# UI_PCB.net
KiCad netlist of a schematic drawn in EAGLE
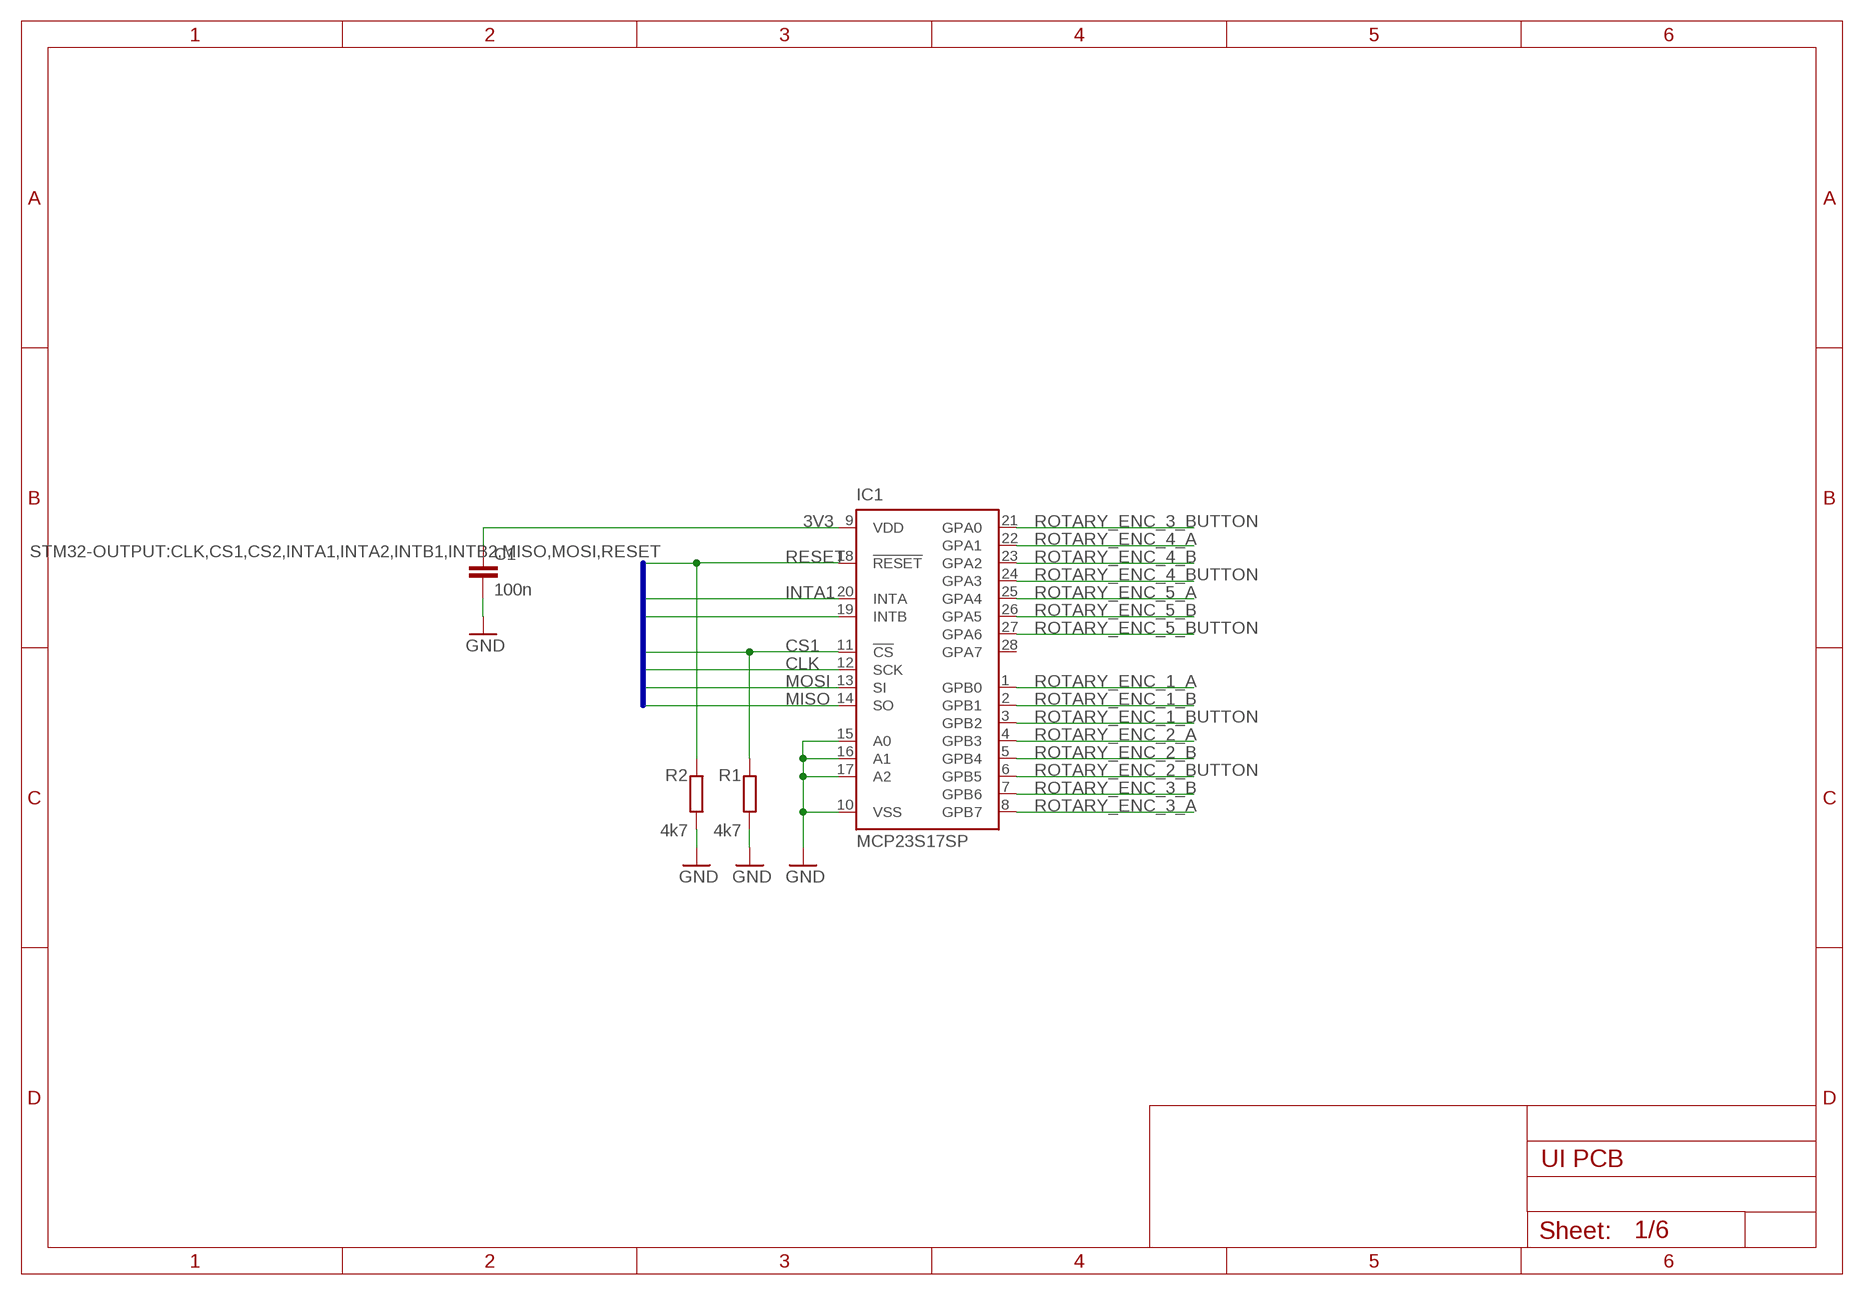
[diagram p0: schematic, sheet 1]
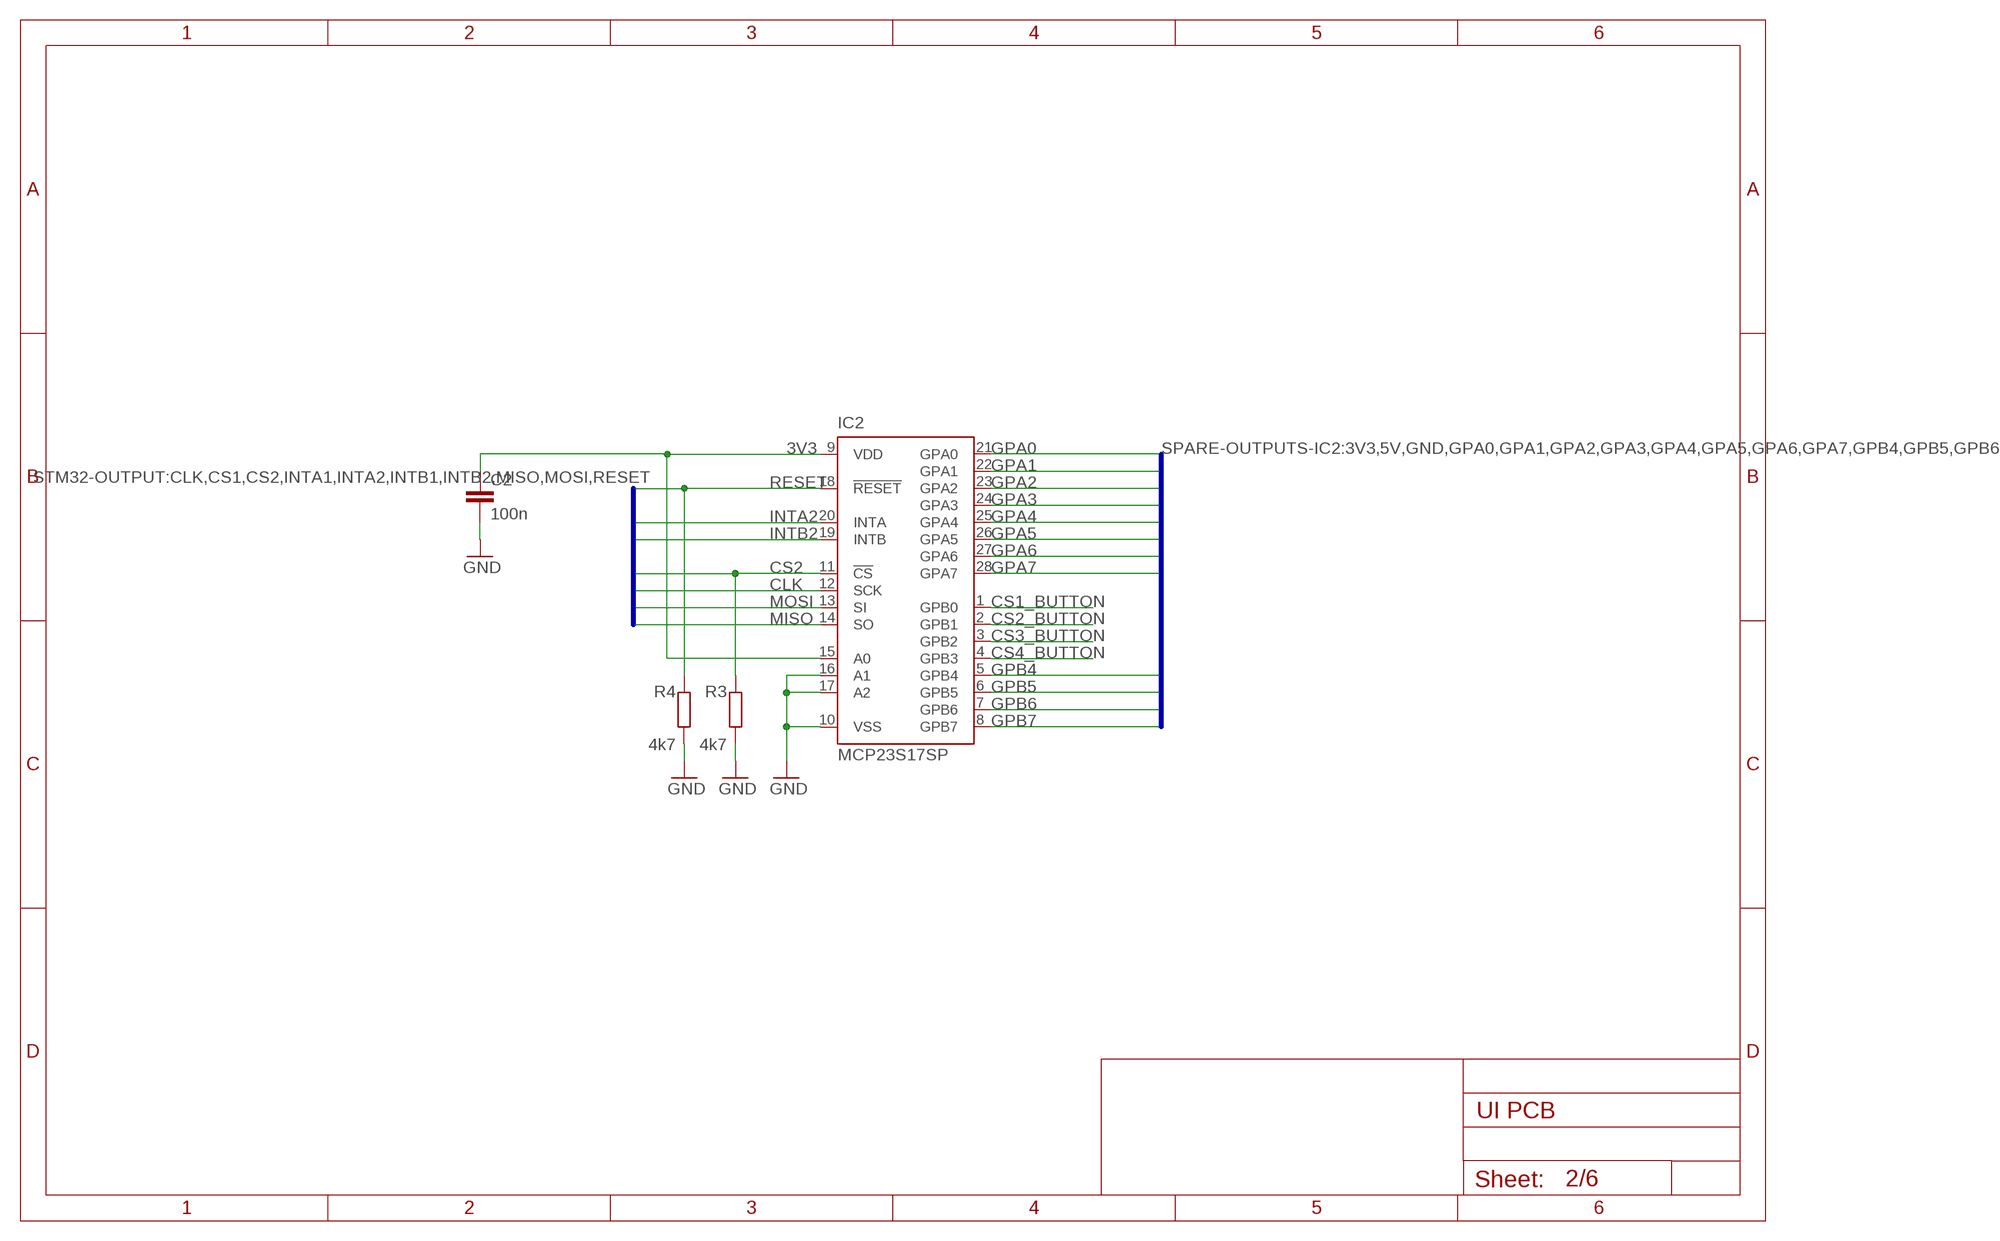
[diagram p1: schematic, sheet 2]
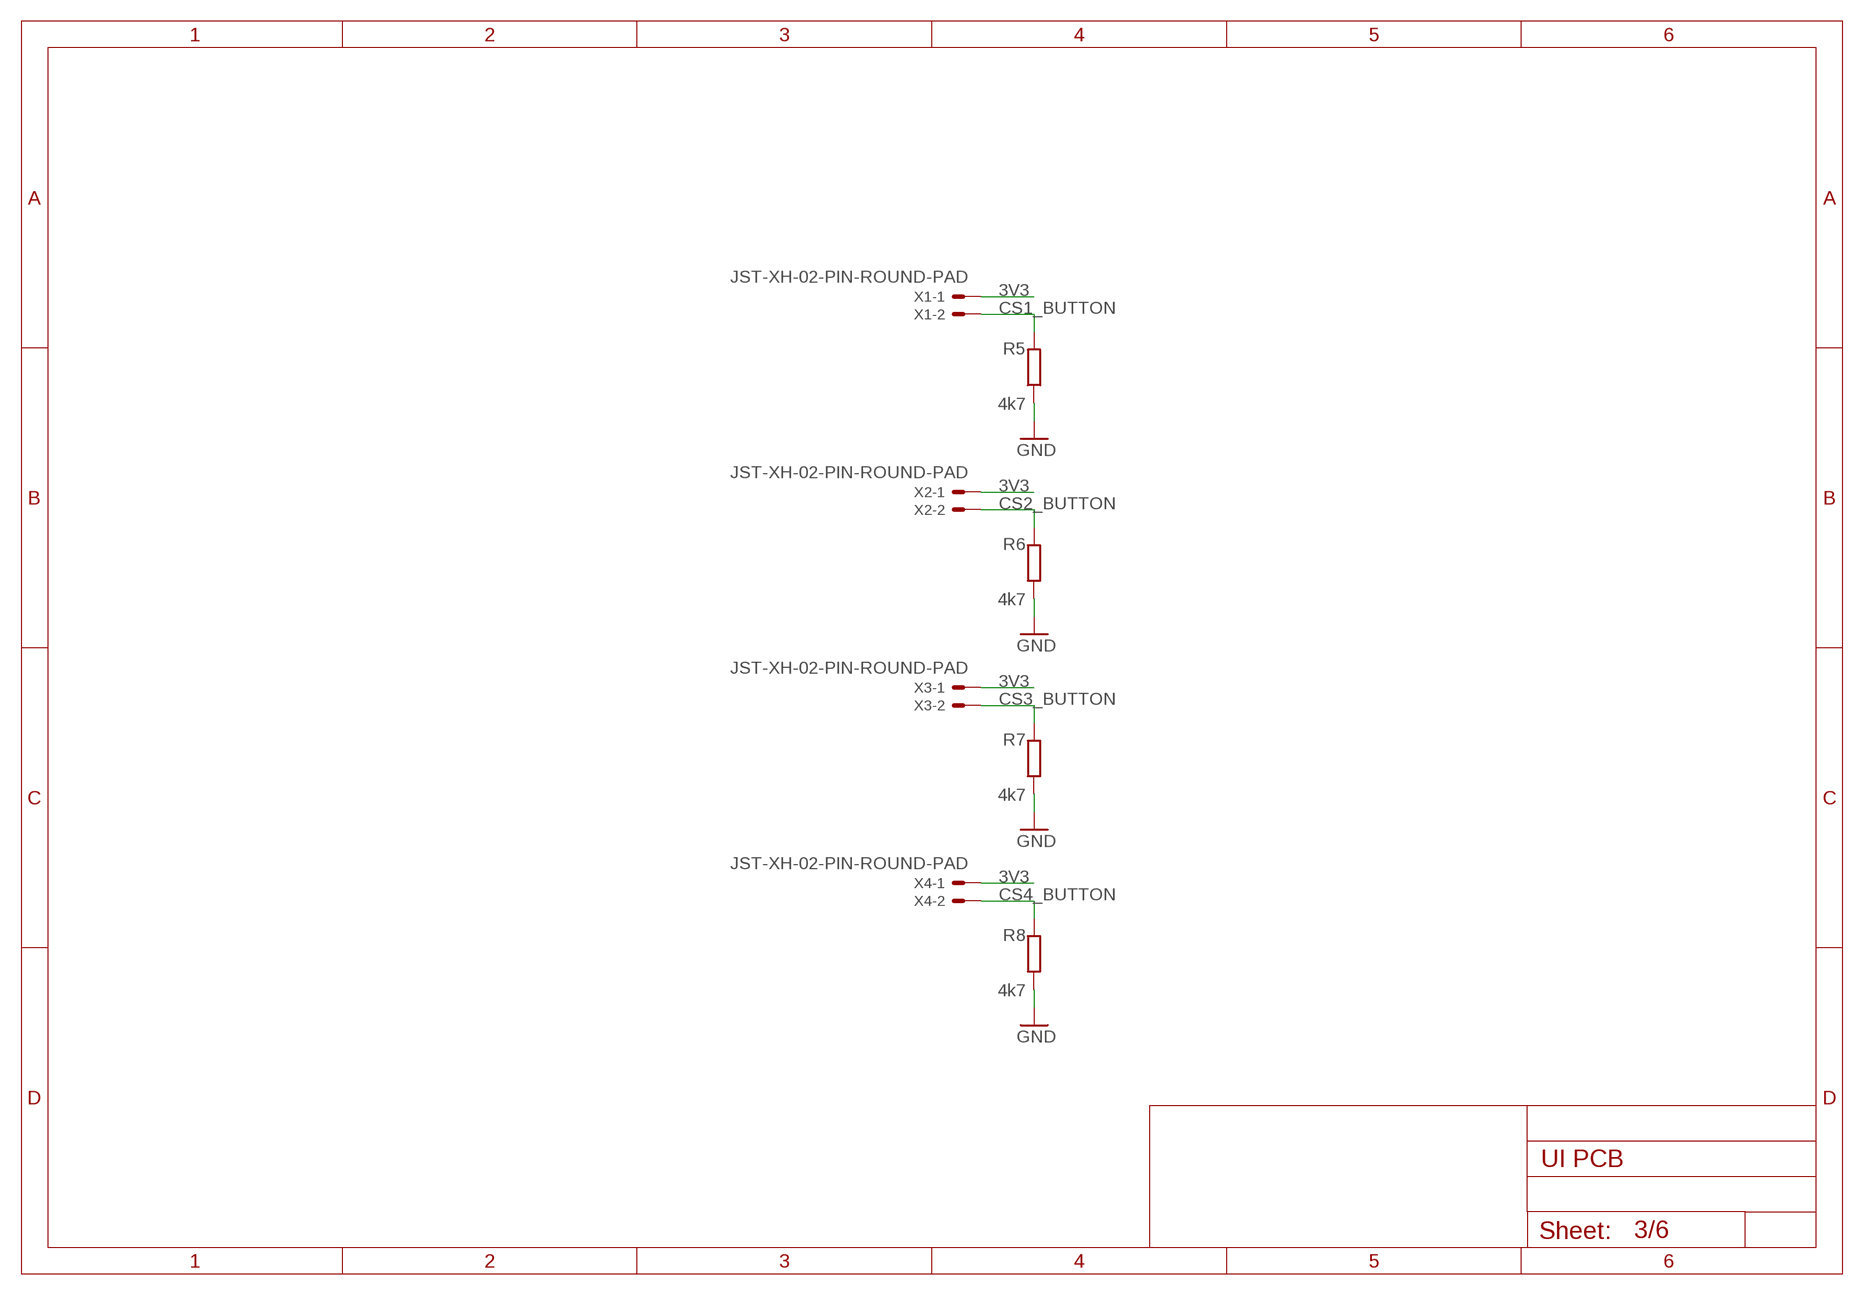
[diagram p2: schematic, sheet 3]
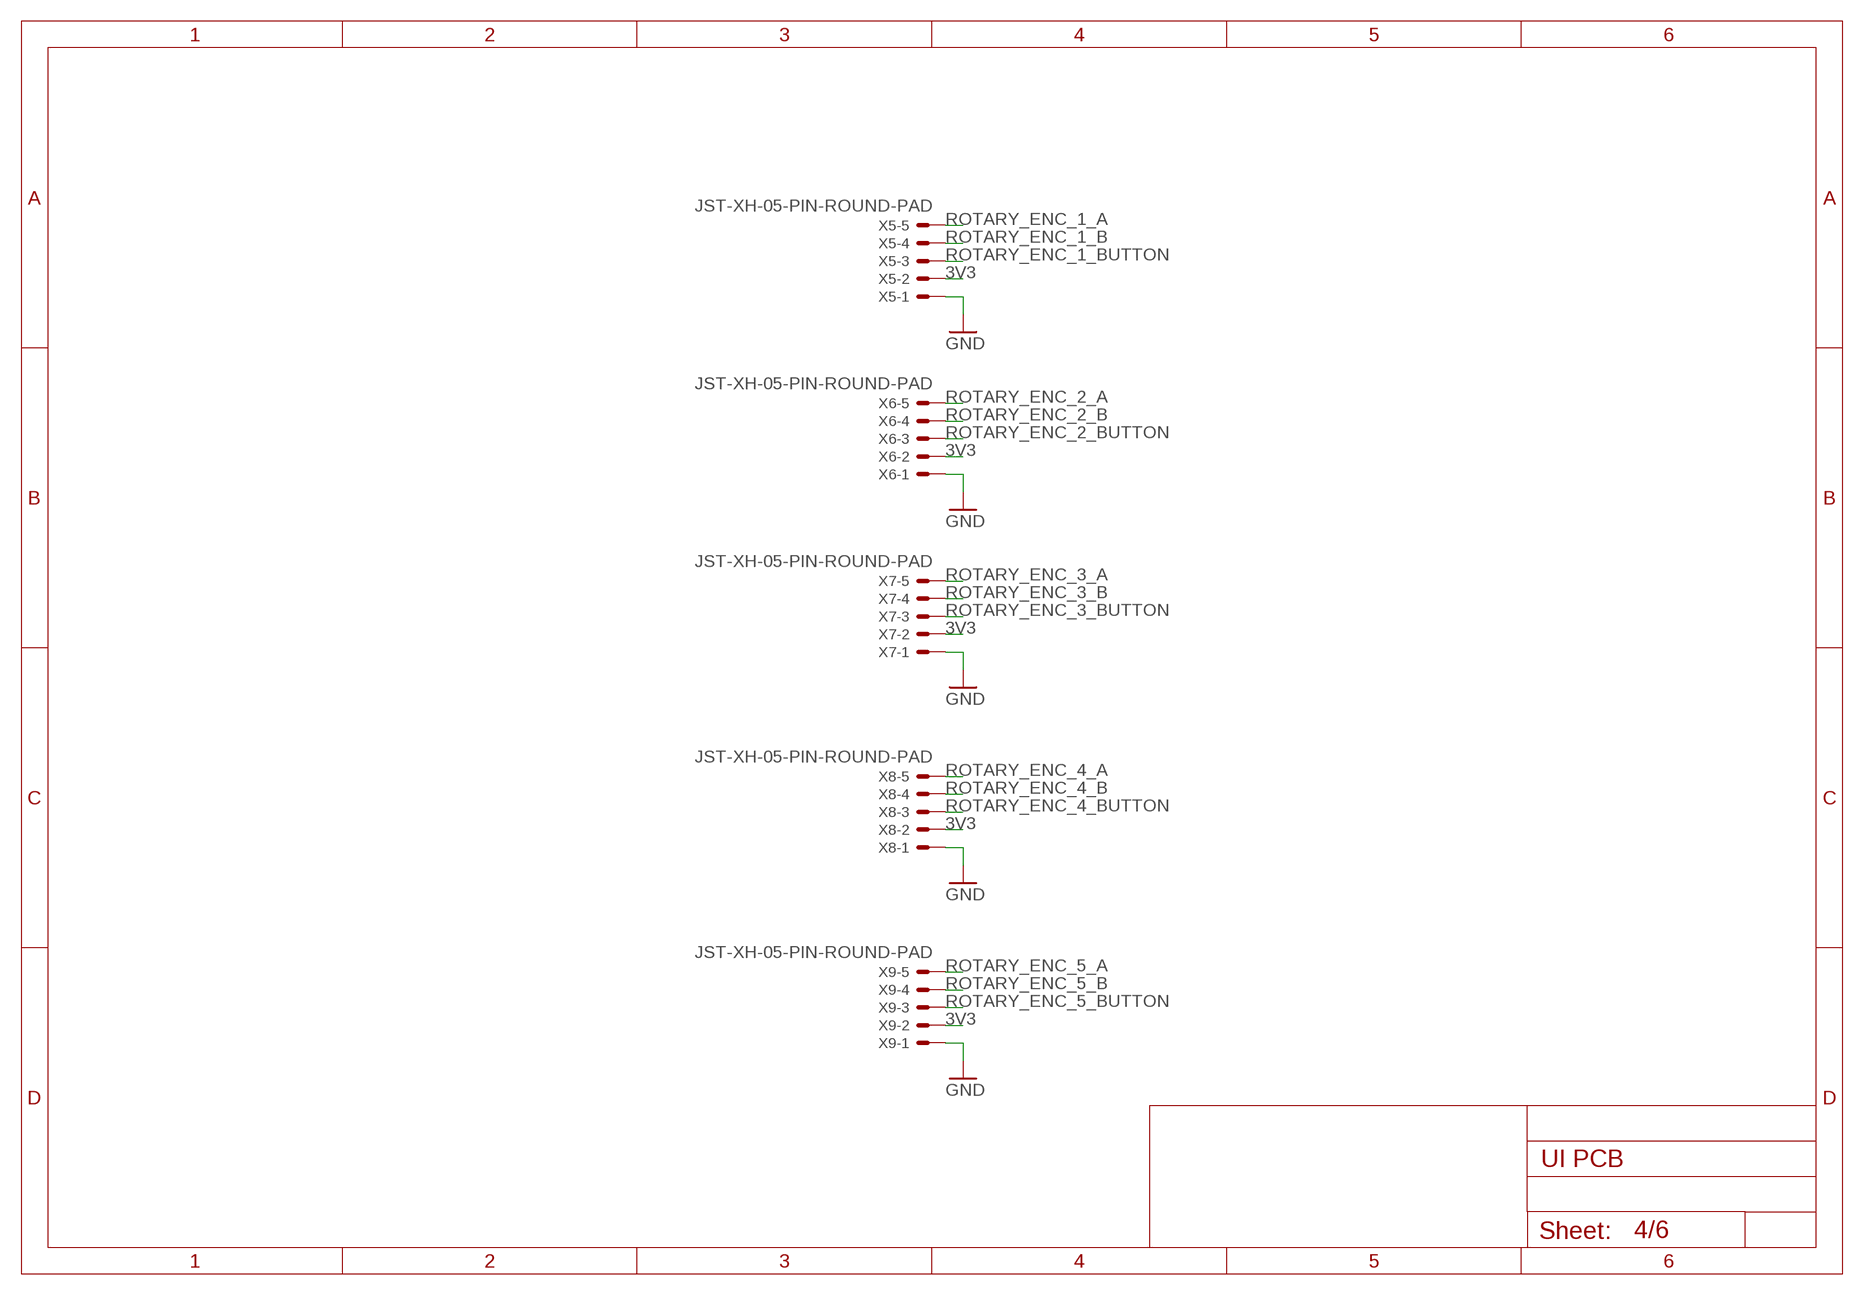
[diagram p3: schematic, sheet 4]
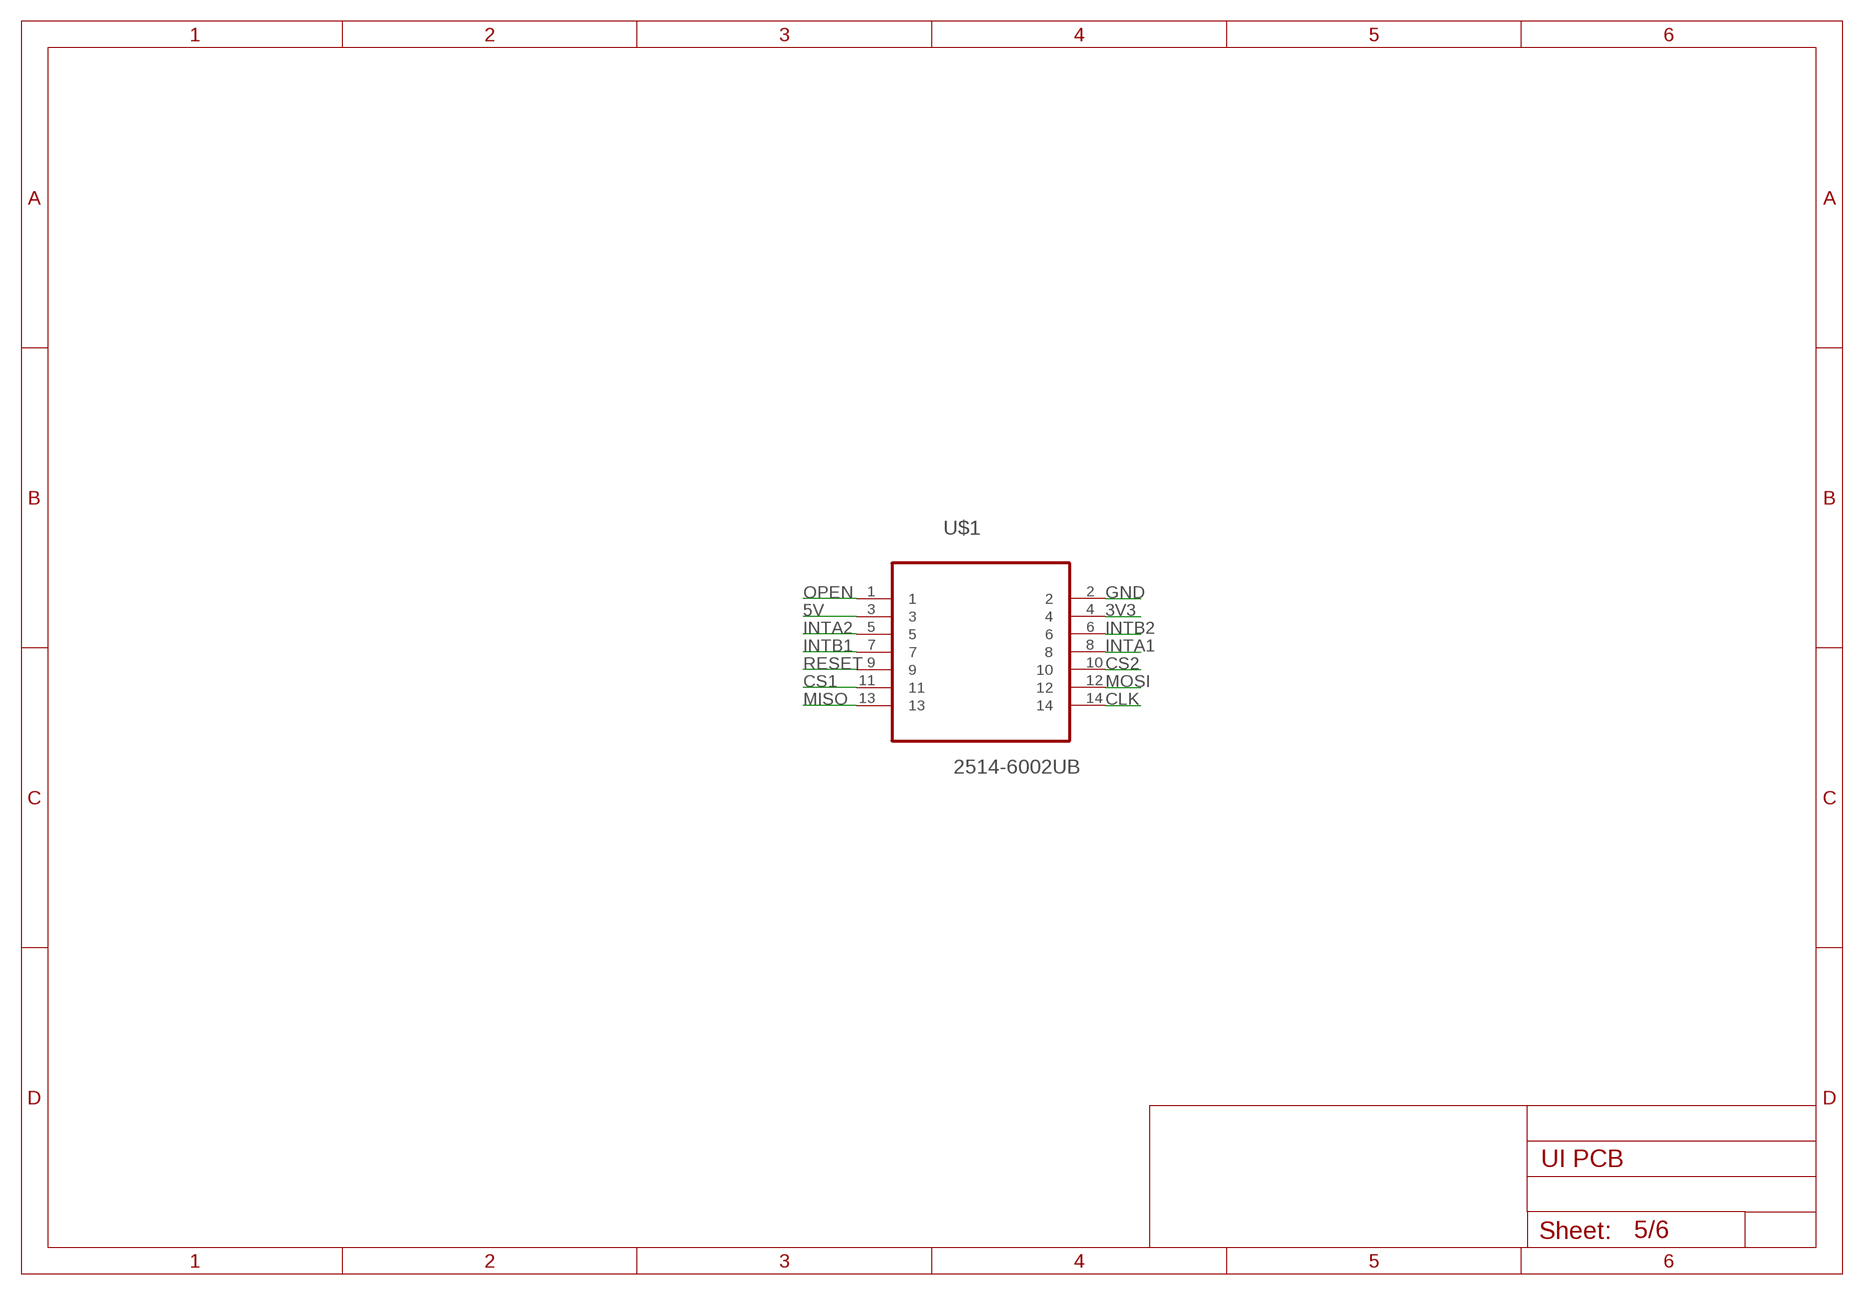
[diagram p4: schematic, sheet 5]
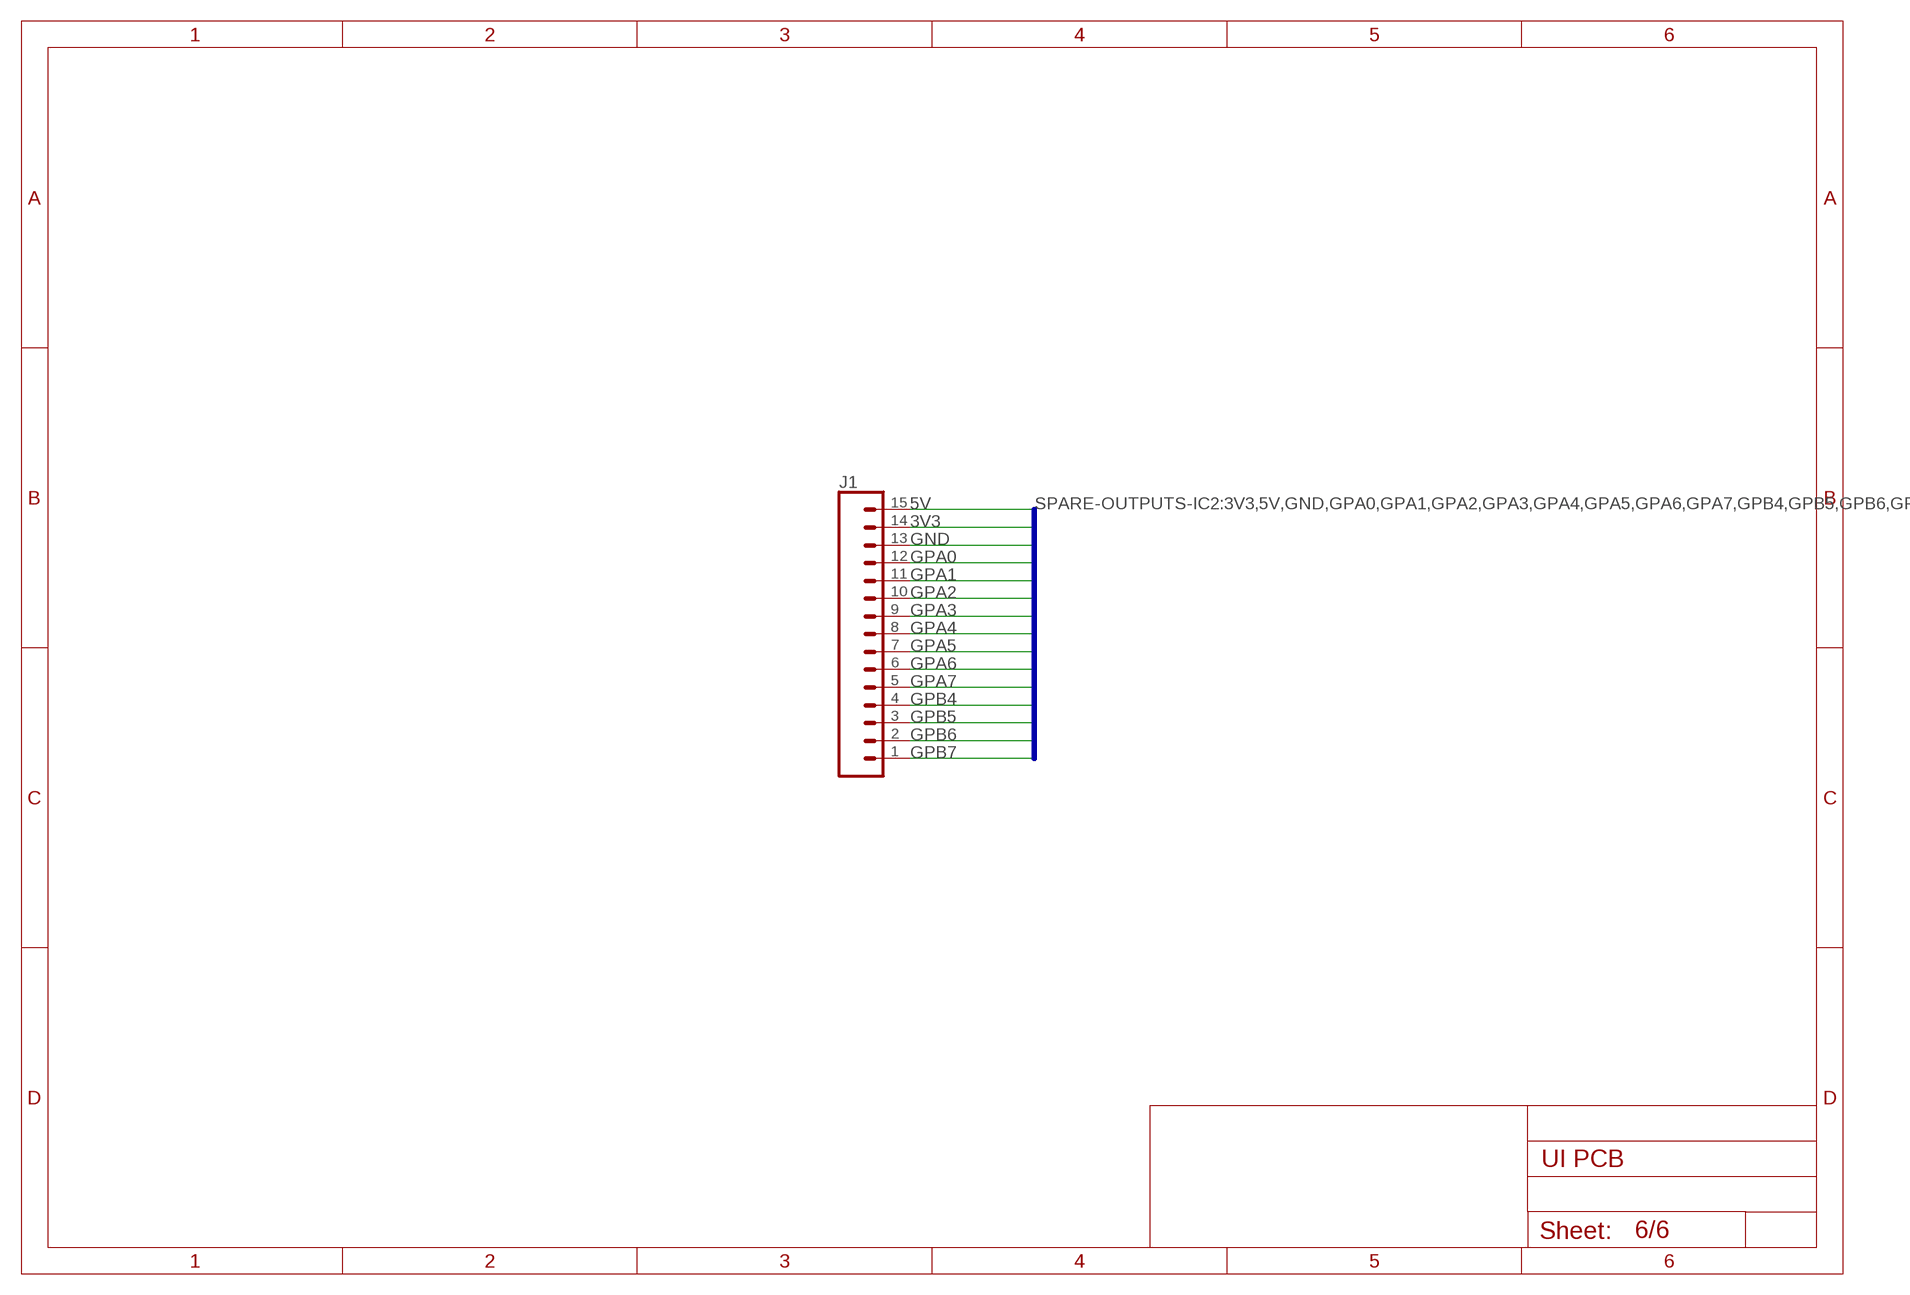
[diagram p5: schematic, sheet 6]

(export (version "E")
  (design (tool "Eeschema 10.0.6"))
  (components
    (comp (ref "J1")
      (value "CONN_15")
      (footprint "eagle-import:1X15")
      (libsource (lib "eagle-import") (part "CONN_15"))
    )
    (comp (ref "C2")
      (value "100n")
      (footprint "eagle-import:C0603")
      (libsource (lib "eagle-import") (part "C-EUC0603"))
    )
    (comp (ref "IC2")
      (value "MCP23S17SP")
      (footprint "eagle-import:DIL28-3")
      (fields (field (name "MF") "MICROCHIP") (field (name "MPN") "MCP23S17-E/SP"))
      (libsource (lib "eagle-import") (part "MCP23S17SP"))
    )
    (comp (ref "R3")
      (value "4k7")
      (footprint "eagle-import:R0805")
      (libsource (lib "eagle-import") (part "R-EU_R0805"))
    )
    (comp (ref "R4")
      (value "4k7")
      (footprint "eagle-import:R0805")
      (libsource (lib "eagle-import") (part "R-EU_R0805"))
    )
    (comp (ref "U$1")
      (value "2514-6002UB")
      (footprint "eagle-import:3M_2514-6002UB")
      (libsource (lib "eagle-import") (part "2514-6002UB"))
    )
    (comp (ref "C1")
      (value "100n")
      (footprint "eagle-import:C0603")
      (libsource (lib "eagle-import") (part "C-EUC0603"))
    )
    (comp (ref "IC1")
      (value "MCP23S17SP")
      (footprint "eagle-import:DIL28-3")
      (fields (field (name "MF") "MICROCHIP") (field (name "MPN") "MCP23S17-E/SP"))
      (libsource (lib "eagle-import") (part "MCP23S17SP"))
    )
    (comp (ref "R1")
      (value "4k7")
      (footprint "eagle-import:R0805")
      (libsource (lib "eagle-import") (part "R-EU_R0805"))
    )
    (comp (ref "R2")
      (value "4k7")
      (footprint "eagle-import:R0805")
      (libsource (lib "eagle-import") (part "R-EU_R0805"))
    )
    (comp (ref "R5")
      (value "4k7")
      (footprint "eagle-import:R0805")
      (libsource (lib "eagle-import") (part "R-EU_R0805"))
    )
    (comp (ref "R6")
      (value "4k7")
      (footprint "eagle-import:R0805")
      (libsource (lib "eagle-import") (part "R-EU_R0805"))
    )
    (comp (ref "R7")
      (value "4k7")
      (footprint "eagle-import:R0805")
      (libsource (lib "eagle-import") (part "R-EU_R0805"))
    )
    (comp (ref "R8")
      (value "4k7")
      (footprint "eagle-import:R0805")
      (libsource (lib "eagle-import") (part "R-EU_R0805"))
    )
    (comp (ref "X1")
      (value "JST-XH-02-PIN-ROUND-PAD")
      (footprint "eagle-import:JST-XH-02-PACKAGE-ROUND-PAD")
      (libsource (lib "eagle-import") (part "JST-XH-02-PIN-ROUND-PAD"))
    )
    (comp (ref "X2")
      (value "JST-XH-02-PIN-ROUND-PAD")
      (footprint "eagle-import:JST-XH-02-PACKAGE-ROUND-PAD")
      (libsource (lib "eagle-import") (part "JST-XH-02-PIN-ROUND-PAD"))
    )
    (comp (ref "X3")
      (value "JST-XH-02-PIN-ROUND-PAD")
      (footprint "eagle-import:JST-XH-02-PACKAGE-ROUND-PAD")
      (libsource (lib "eagle-import") (part "JST-XH-02-PIN-ROUND-PAD"))
    )
    (comp (ref "X4")
      (value "JST-XH-02-PIN-ROUND-PAD")
      (footprint "eagle-import:JST-XH-02-PACKAGE-ROUND-PAD")
      (libsource (lib "eagle-import") (part "JST-XH-02-PIN-ROUND-PAD"))
    )
    (comp (ref "X5")
      (value "JST-XH-05-PIN-ROUND-PAD")
      (footprint "eagle-import:JST-XH-05-PACKAGE-ROUND-PAD")
      (libsource (lib "eagle-import") (part "JST-XH-05-PIN-ROUND-PAD"))
    )
    (comp (ref "X6")
      (value "JST-XH-05-PIN-ROUND-PAD")
      (footprint "eagle-import:JST-XH-05-PACKAGE-ROUND-PAD")
      (libsource (lib "eagle-import") (part "JST-XH-05-PIN-ROUND-PAD"))
    )
    (comp (ref "X7")
      (value "JST-XH-05-PIN-ROUND-PAD")
      (footprint "eagle-import:JST-XH-05-PACKAGE-ROUND-PAD")
      (libsource (lib "eagle-import") (part "JST-XH-05-PIN-ROUND-PAD"))
    )
    (comp (ref "X8")
      (value "JST-XH-05-PIN-ROUND-PAD")
      (footprint "eagle-import:JST-XH-05-PACKAGE-ROUND-PAD")
      (libsource (lib "eagle-import") (part "JST-XH-05-PIN-ROUND-PAD"))
    )
    (comp (ref "X9")
      (value "JST-XH-05-PIN-ROUND-PAD")
      (footprint "eagle-import:JST-XH-05-PACKAGE-ROUND-PAD")
      (libsource (lib "eagle-import") (part "JST-XH-05-PIN-ROUND-PAD"))
    )
  )
  (nets
    (net (code "11") (name "3V3") (class "Default")
      (node (ref "C1") (pin "1") (pinfunction "1_1") (pintype "passive"))
      (node (ref "C2") (pin "1") (pinfunction "1_1") (pintype "passive"))
      (node (ref "IC1") (pin "9") (pinfunction "VDD_9") (pintype "power_in"))
      (node (ref "IC2") (pin "15") (pinfunction "A0_15") (pintype "input"))
      (node (ref "IC2") (pin "9") (pinfunction "VDD_9") (pintype "power_in"))
      (node (ref "J1") (pin "14") (pinfunction "14_14") (pintype "passive"))
      (node (ref "U$1") (pin "4") (pinfunction "4_4") (pintype "passive"))
      (node (ref "X1") (pin "1") (pinfunction "S_1") (pintype "passive"))
      (node (ref "X2") (pin "1") (pinfunction "S_1") (pintype "passive"))
      (node (ref "X3") (pin "1") (pinfunction "S_1") (pintype "passive"))
      (node (ref "X4") (pin "1") (pinfunction "S_1") (pintype "passive"))
      (node (ref "X5") (pin "2") (pinfunction "S_2") (pintype "passive"))
      (node (ref "X6") (pin "2") (pinfunction "S_2") (pintype "passive"))
      (node (ref "X7") (pin "2") (pinfunction "S_2") (pintype "passive"))
      (node (ref "X8") (pin "2") (pinfunction "S_2") (pintype "passive"))
      (node (ref "X9") (pin "2") (pinfunction "S_2") (pintype "passive"))
    )
    (net (code "12") (name "5V") (class "Default")
      (node (ref "J1") (pin "15") (pinfunction "15_15") (pintype "passive"))
      (node (ref "U$1") (pin "3") (pinfunction "3_3") (pintype "passive"))
    )
    (net (code "13") (name "CLK") (class "Default")
      (node (ref "IC1") (pin "12") (pinfunction "SCK_12") (pintype "input"))
      (node (ref "IC2") (pin "12") (pinfunction "SCK_12") (pintype "input"))
      (node (ref "U$1") (pin "14") (pinfunction "14_14") (pintype "passive"))
    )
    (net (code "14") (name "CS1") (class "Default")
      (node (ref "IC1") (pin "11") (pinfunction "~{CS}_11") (pintype "input"))
      (node (ref "R1") (pin "2") (pinfunction "2_2") (pintype "passive"))
      (node (ref "U$1") (pin "11") (pinfunction "11_11") (pintype "passive"))
    )
    (net (code "15") (name "CS1_BUTTON") (class "Default")
      (node (ref "IC2") (pin "1") (pinfunction "GPB0_1") (pintype "bidirectional"))
      (node (ref "R5") (pin "2") (pinfunction "2_2") (pintype "passive"))
      (node (ref "X1") (pin "2") (pinfunction "S_2") (pintype "passive"))
    )
    (net (code "16") (name "CS2") (class "Default")
      (node (ref "IC2") (pin "11") (pinfunction "~{CS}_11") (pintype "input"))
      (node (ref "R3") (pin "2") (pinfunction "2_2") (pintype "passive"))
      (node (ref "U$1") (pin "10") (pinfunction "10_10") (pintype "passive"))
    )
    (net (code "17") (name "CS2_BUTTON") (class "Default")
      (node (ref "IC2") (pin "2") (pinfunction "GPB1_2") (pintype "bidirectional"))
      (node (ref "R6") (pin "2") (pinfunction "2_2") (pintype "passive"))
      (node (ref "X2") (pin "2") (pinfunction "S_2") (pintype "passive"))
    )
    (net (code "18") (name "CS3_BUTTON") (class "Default")
      (node (ref "IC2") (pin "3") (pinfunction "GPB2_3") (pintype "bidirectional"))
      (node (ref "R7") (pin "2") (pinfunction "2_2") (pintype "passive"))
      (node (ref "X3") (pin "2") (pinfunction "S_2") (pintype "passive"))
    )
    (net (code "19") (name "CS4_BUTTON") (class "Default")
      (node (ref "IC2") (pin "4") (pinfunction "GPB3_4") (pintype "bidirectional"))
      (node (ref "R8") (pin "2") (pinfunction "2_2") (pintype "passive"))
      (node (ref "X4") (pin "2") (pinfunction "S_2") (pintype "passive"))
    )
    (net (code "20") (name "GND") (class "Default")
      (node (ref "C1") (pin "2") (pinfunction "2_2") (pintype "passive"))
      (node (ref "C2") (pin "2") (pinfunction "2_2") (pintype "passive"))
      (node (ref "IC1") (pin "10") (pinfunction "VSS_10") (pintype "power_in"))
      (node (ref "IC1") (pin "15") (pinfunction "A0_15") (pintype "input"))
      (node (ref "IC1") (pin "16") (pinfunction "A1_16") (pintype "input"))
      (node (ref "IC1") (pin "17") (pinfunction "A2_17") (pintype "input"))
      (node (ref "IC2") (pin "10") (pinfunction "VSS_10") (pintype "power_in"))
      (node (ref "IC2") (pin "16") (pinfunction "A1_16") (pintype "input"))
      (node (ref "IC2") (pin "17") (pinfunction "A2_17") (pintype "input"))
      (node (ref "J1") (pin "13") (pinfunction "13_13") (pintype "passive"))
      (node (ref "R1") (pin "1") (pinfunction "1_1") (pintype "passive"))
      (node (ref "R2") (pin "1") (pinfunction "1_1") (pintype "passive"))
      (node (ref "R3") (pin "1") (pinfunction "1_1") (pintype "passive"))
      (node (ref "R4") (pin "1") (pinfunction "1_1") (pintype "passive"))
      (node (ref "R5") (pin "1") (pinfunction "1_1") (pintype "passive"))
      (node (ref "R6") (pin "1") (pinfunction "1_1") (pintype "passive"))
      (node (ref "R7") (pin "1") (pinfunction "1_1") (pintype "passive"))
      (node (ref "R8") (pin "1") (pinfunction "1_1") (pintype "passive"))
      (node (ref "U$1") (pin "2") (pinfunction "2_2") (pintype "passive"))
      (node (ref "X5") (pin "1") (pinfunction "S_1") (pintype "passive"))
      (node (ref "X6") (pin "1") (pinfunction "S_1") (pintype "passive"))
      (node (ref "X7") (pin "1") (pinfunction "S_1") (pintype "passive"))
      (node (ref "X8") (pin "1") (pinfunction "S_1") (pintype "passive"))
      (node (ref "X9") (pin "1") (pinfunction "S_1") (pintype "passive"))
    )
    (net (code "21") (name "GPA0") (class "Default")
      (node (ref "IC2") (pin "21") (pinfunction "GPA0_21") (pintype "bidirectional"))
      (node (ref "J1") (pin "12") (pinfunction "12_12") (pintype "passive"))
    )
    (net (code "22") (name "GPA1") (class "Default")
      (node (ref "IC2") (pin "22") (pinfunction "GPA1_22") (pintype "bidirectional"))
      (node (ref "J1") (pin "11") (pinfunction "11_11") (pintype "passive"))
    )
    (net (code "23") (name "GPA2") (class "Default")
      (node (ref "IC2") (pin "23") (pinfunction "GPA2_23") (pintype "bidirectional"))
      (node (ref "J1") (pin "10") (pinfunction "10_10") (pintype "passive"))
    )
    (net (code "24") (name "GPA3") (class "Default")
      (node (ref "IC2") (pin "24") (pinfunction "GPA3_24") (pintype "bidirectional"))
      (node (ref "J1") (pin "9") (pinfunction "9_9") (pintype "passive"))
    )
    (net (code "25") (name "GPA4") (class "Default")
      (node (ref "IC2") (pin "25") (pinfunction "GPA4_25") (pintype "bidirectional"))
      (node (ref "J1") (pin "8") (pinfunction "8_8") (pintype "passive"))
    )
    (net (code "26") (name "GPA5") (class "Default")
      (node (ref "IC2") (pin "26") (pinfunction "GPA5_26") (pintype "bidirectional"))
      (node (ref "J1") (pin "7") (pinfunction "7_7") (pintype "passive"))
    )
    (net (code "27") (name "GPA6") (class "Default")
      (node (ref "IC2") (pin "27") (pinfunction "GPA6_27") (pintype "bidirectional"))
      (node (ref "J1") (pin "6") (pinfunction "6_6") (pintype "passive"))
    )
    (net (code "28") (name "GPA7") (class "Default")
      (node (ref "IC2") (pin "28") (pinfunction "GPA7_28") (pintype "bidirectional"))
      (node (ref "J1") (pin "5") (pinfunction "5_5") (pintype "passive"))
    )
    (net (code "29") (name "GPB4") (class "Default")
      (node (ref "IC2") (pin "5") (pinfunction "GPB4_5") (pintype "bidirectional"))
      (node (ref "J1") (pin "4") (pinfunction "4_4") (pintype "passive"))
    )
    (net (code "30") (name "GPB5") (class "Default")
      (node (ref "IC2") (pin "6") (pinfunction "GPB5_6") (pintype "bidirectional"))
      (node (ref "J1") (pin "3") (pinfunction "3_3") (pintype "passive"))
    )
    (net (code "31") (name "GPB6") (class "Default")
      (node (ref "IC2") (pin "7") (pinfunction "GPB6_7") (pintype "bidirectional"))
      (node (ref "J1") (pin "2") (pinfunction "2_2") (pintype "passive"))
    )
    (net (code "32") (name "GPB7") (class "Default")
      (node (ref "IC2") (pin "8") (pinfunction "GPB7_8") (pintype "bidirectional"))
      (node (ref "J1") (pin "1") (pinfunction "1_1") (pintype "passive"))
    )
    (net (code "33") (name "INTA1") (class "Default")
      (node (ref "IC1") (pin "20") (pinfunction "INTA_20") (pintype "output"))
      (node (ref "U$1") (pin "8") (pinfunction "8_8") (pintype "passive"))
    )
    (net (code "34") (name "INTA2") (class "Default")
      (node (ref "IC2") (pin "20") (pinfunction "INTA_20") (pintype "output"))
      (node (ref "U$1") (pin "5") (pinfunction "5_5") (pintype "passive"))
    )
    (net (code "35") (name "INTB1") (class "Default")
      (node (ref "IC1") (pin "19") (pinfunction "INTB_19") (pintype "output"))
      (node (ref "U$1") (pin "7") (pinfunction "7_7") (pintype "passive"))
    )
    (net (code "36") (name "INTB2") (class "Default")
      (node (ref "IC2") (pin "19") (pinfunction "INTB_19") (pintype "output"))
      (node (ref "U$1") (pin "6") (pinfunction "6_6") (pintype "passive"))
    )
    (net (code "37") (name "MISO") (class "Default")
      (node (ref "IC1") (pin "14") (pinfunction "SO_14") (pintype "output"))
      (node (ref "IC2") (pin "14") (pinfunction "SO_14") (pintype "output"))
      (node (ref "U$1") (pin "13") (pinfunction "13_13") (pintype "passive"))
    )
    (net (code "38") (name "MOSI") (class "Default")
      (node (ref "IC1") (pin "13") (pinfunction "SI_13") (pintype "input"))
      (node (ref "IC2") (pin "13") (pinfunction "SI_13") (pintype "input"))
      (node (ref "U$1") (pin "12") (pinfunction "12_12") (pintype "passive"))
    )
    (net (code "39") (name "OPEN") (class "Default")
      (node (ref "U$1") (pin "1") (pinfunction "1_1") (pintype "passive"))
    )
    (net (code "40") (name "RESET") (class "Default")
      (node (ref "IC1") (pin "18") (pinfunction "~{RESET}_18") (pintype "input"))
      (node (ref "IC2") (pin "18") (pinfunction "~{RESET}_18") (pintype "input"))
      (node (ref "R2") (pin "2") (pinfunction "2_2") (pintype "passive"))
      (node (ref "R4") (pin "2") (pinfunction "2_2") (pintype "passive"))
      (node (ref "U$1") (pin "9") (pinfunction "9_9") (pintype "passive"))
    )
    (net (code "41") (name "ROTARY_ENC_1_A") (class "Default")
      (node (ref "IC1") (pin "1") (pinfunction "GPB0_1") (pintype "bidirectional"))
      (node (ref "X5") (pin "5") (pinfunction "S_5") (pintype "passive"))
    )
    (net (code "42") (name "ROTARY_ENC_1_B") (class "Default")
      (node (ref "IC1") (pin "2") (pinfunction "GPB1_2") (pintype "bidirectional"))
      (node (ref "X5") (pin "4") (pinfunction "S_4") (pintype "passive"))
    )
    (net (code "43") (name "ROTARY_ENC_1_BUTTON") (class "Default")
      (node (ref "IC1") (pin "3") (pinfunction "GPB2_3") (pintype "bidirectional"))
      (node (ref "X5") (pin "3") (pinfunction "S_3") (pintype "passive"))
    )
    (net (code "44") (name "ROTARY_ENC_2_A") (class "Default")
      (node (ref "IC1") (pin "4") (pinfunction "GPB3_4") (pintype "bidirectional"))
      (node (ref "X6") (pin "5") (pinfunction "S_5") (pintype "passive"))
    )
    (net (code "45") (name "ROTARY_ENC_2_B") (class "Default")
      (node (ref "IC1") (pin "5") (pinfunction "GPB4_5") (pintype "bidirectional"))
      (node (ref "X6") (pin "4") (pinfunction "S_4") (pintype "passive"))
    )
    (net (code "46") (name "ROTARY_ENC_2_BUTTON") (class "Default")
      (node (ref "IC1") (pin "6") (pinfunction "GPB5_6") (pintype "bidirectional"))
      (node (ref "X6") (pin "3") (pinfunction "S_3") (pintype "passive"))
    )
    (net (code "47") (name "ROTARY_ENC_3_A") (class "Default")
      (node (ref "IC1") (pin "8") (pinfunction "GPB7_8") (pintype "bidirectional"))
      (node (ref "X7") (pin "5") (pinfunction "S_5") (pintype "passive"))
    )
    (net (code "48") (name "ROTARY_ENC_3_B") (class "Default")
      (node (ref "IC1") (pin "7") (pinfunction "GPB6_7") (pintype "bidirectional"))
      (node (ref "X7") (pin "4") (pinfunction "S_4") (pintype "passive"))
    )
    (net (code "49") (name "ROTARY_ENC_3_BUTTON") (class "Default")
      (node (ref "IC1") (pin "21") (pinfunction "GPA0_21") (pintype "bidirectional"))
      (node (ref "X7") (pin "3") (pinfunction "S_3") (pintype "passive"))
    )
    (net (code "50") (name "ROTARY_ENC_4_A") (class "Default")
      (node (ref "IC1") (pin "22") (pinfunction "GPA1_22") (pintype "bidirectional"))
      (node (ref "X8") (pin "5") (pinfunction "S_5") (pintype "passive"))
    )
    (net (code "51") (name "ROTARY_ENC_4_B") (class "Default")
      (node (ref "IC1") (pin "23") (pinfunction "GPA2_23") (pintype "bidirectional"))
      (node (ref "X8") (pin "4") (pinfunction "S_4") (pintype "passive"))
    )
    (net (code "52") (name "ROTARY_ENC_4_BUTTON") (class "Default")
      (node (ref "IC1") (pin "24") (pinfunction "GPA3_24") (pintype "bidirectional"))
      (node (ref "X8") (pin "3") (pinfunction "S_3") (pintype "passive"))
    )
    (net (code "53") (name "ROTARY_ENC_5_A") (class "Default")
      (node (ref "IC1") (pin "25") (pinfunction "GPA4_25") (pintype "bidirectional"))
      (node (ref "X9") (pin "5") (pinfunction "S_5") (pintype "passive"))
    )
    (net (code "54") (name "ROTARY_ENC_5_B") (class "Default")
      (node (ref "IC1") (pin "26") (pinfunction "GPA5_26") (pintype "bidirectional"))
      (node (ref "X9") (pin "4") (pinfunction "S_4") (pintype "passive"))
    )
    (net (code "55") (name "ROTARY_ENC_5_BUTTON") (class "Default")
      (node (ref "IC1") (pin "27") (pinfunction "GPA6_27") (pintype "bidirectional"))
      (node (ref "X9") (pin "3") (pinfunction "S_3") (pintype "passive"))
    )
    (net (code "56") (name "unconnected-(IC1-GPA7-Pad28)") (class "Default")
      (node (ref "IC1") (pin "28") (pinfunction "GPA7_28") (pintype "bidirectional"))
    )
  )
)
